# FPGA_JTAG.net
KiCad netlist of a schematic drawn in Altium Designer
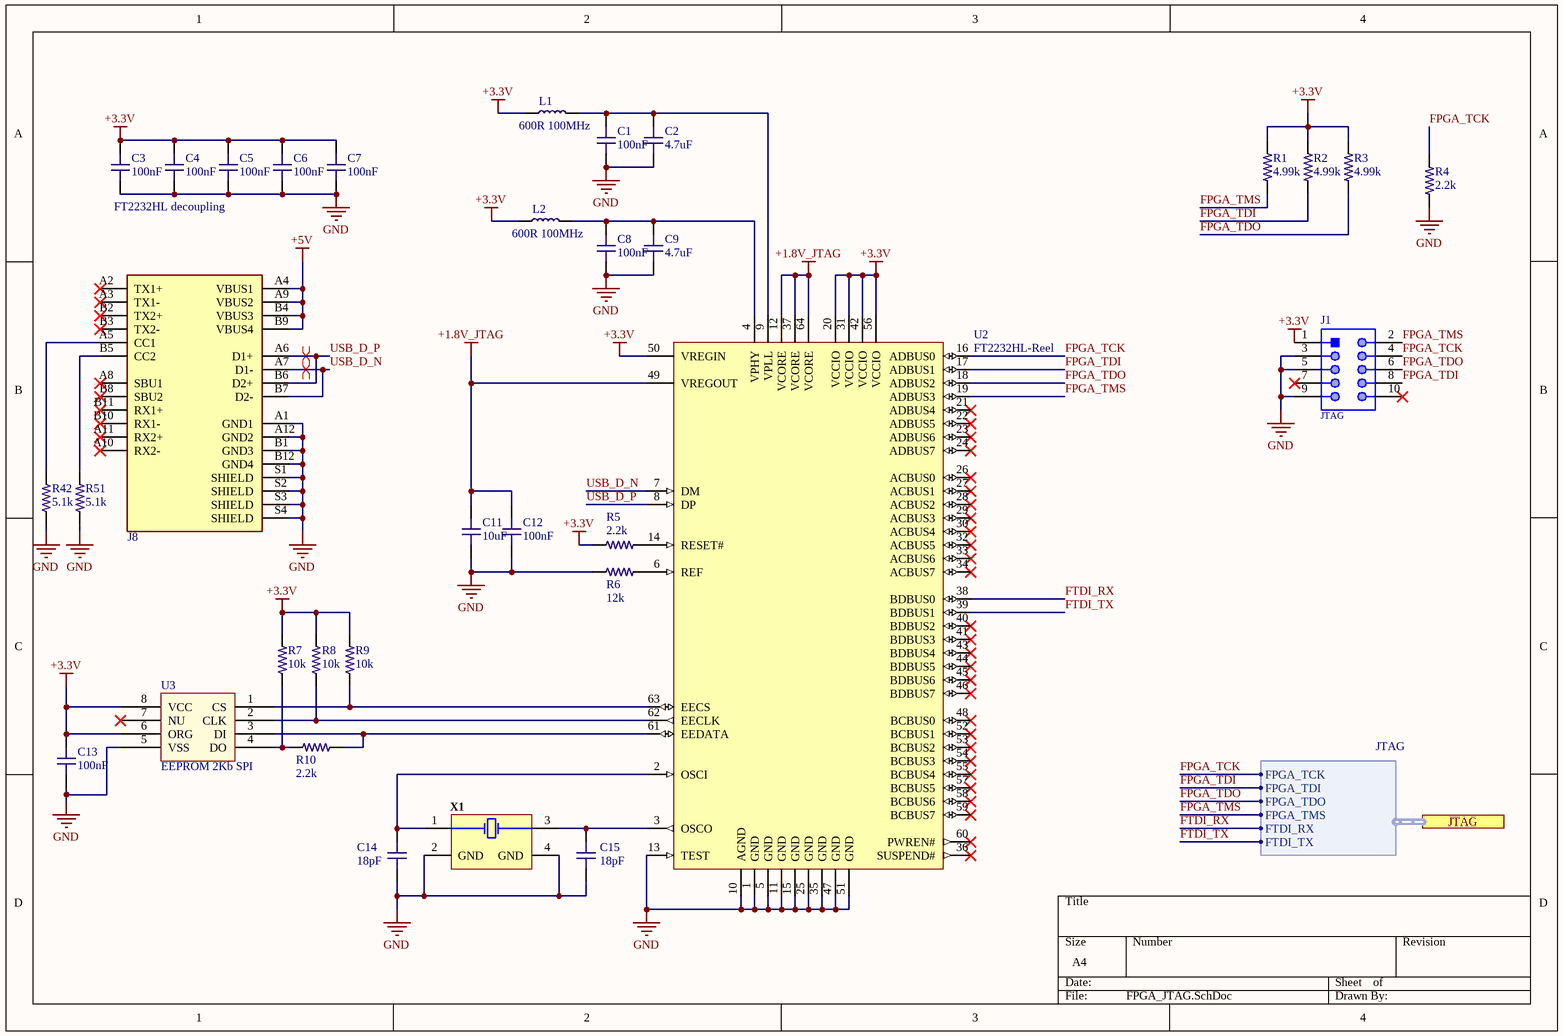
[diagram p0: FPGA_JTAG.SchDoc]

(export (version "E")
  (design (tool "Eeschema 10.0.6"))
  (components
    (comp (ref "C1")
      (value "100nF")
      (footprint "C0603-HIGH-DENSITY")
      (description "Chip Capacitor, 0603, 100nF, 25V, X7R")
      (fields (field (name "Comment") "C0603 100nF 25V X7R"))
      (libsource (lib "Capacitors") (part "C0603 100nF 25V X7R"))
    )
    (comp (ref "C2")
      (value "4.7uF")
      (footprint "C0603-HIGH-DENSITY")
      (description "Chip Capacitor, 0603, 4.7uF, 10V, X5R")
      (fields (field (name "Comment") "C0603 4.7uF 6.3V X5R"))
      (libsource (lib "Capacitors") (part "C0402 4.7uF 6.3V X5R"))
    )
    (comp (ref "C3")
      (value "100nF")
      (footprint "C0603-HIGH-DENSITY")
      (description "Chip Capacitor, 0603, 100nF, 25V, X7R")
      (fields (field (name "Comment") "C0603 100nF 25V X7R"))
      (libsource (lib "Capacitors") (part "C0603 100nF 25V X7R"))
    )
    (comp (ref "C4")
      (value "100nF")
      (footprint "C0603-HIGH-DENSITY")
      (description "Chip Capacitor, 0603, 100nF, 25V, X7R")
      (fields (field (name "Comment") "C0603 100nF 25V X7R"))
      (libsource (lib "Capacitors") (part "C0603 100nF 25V X7R"))
    )
    (comp (ref "C5")
      (value "100nF")
      (footprint "C0603-HIGH-DENSITY")
      (description "Chip Capacitor, 0603, 100nF, 25V, X7R")
      (fields (field (name "Comment") "C0603 100nF 25V X7R"))
      (libsource (lib "Capacitors") (part "C0603 100nF 25V X7R"))
    )
    (comp (ref "C6")
      (value "100nF")
      (footprint "C0603-HIGH-DENSITY")
      (description "Chip Capacitor, 0603, 100nF, 25V, X7R")
      (fields (field (name "Comment") "C0603 100nF 25V X7R"))
      (libsource (lib "Capacitors") (part "C0603 100nF 25V X7R"))
    )
    (comp (ref "C7")
      (value "100nF")
      (footprint "C0603-HIGH-DENSITY")
      (description "Chip Capacitor, 0603, 100nF, 25V, X7R")
      (fields (field (name "Comment") "C0603 100nF 25V X7R"))
      (libsource (lib "Capacitors") (part "C0603 100nF 25V X7R"))
    )
    (comp (ref "C8")
      (value "100nF")
      (footprint "C0603-HIGH-DENSITY")
      (description "Chip Capacitor, 0603, 100nF, 25V, X7R")
      (fields (field (name "Comment") "C0603 100nF 25V X7R"))
      (libsource (lib "Capacitors") (part "C0603 100nF 25V X7R"))
    )
    (comp (ref "C9")
      (value "4.7uF")
      (footprint "C0603-HIGH-DENSITY")
      (description "Chip Capacitor, 0603, 4.7uF, 10V, X5R")
      (fields (field (name "Comment") "C0603 4.7uF 6.3V X5R"))
      (libsource (lib "Capacitors") (part "C0402 4.7uF 6.3V X5R"))
    )
    (comp (ref "C11")
      (value "10uF")
      (footprint "C0603-HIGH-DENSITY")
      (description "Chip Capacitor, 0603, 10uF, 10V, X5R")
      (fields (field (name "Comment") "C0603 10uF 10V X5R"))
      (libsource (lib "Capacitors") (part "C0603 10uF 10V X5R"))
    )
    (comp (ref "C12")
      (value "100nF")
      (footprint "C0603-HIGH-DENSITY")
      (description "Chip Capacitor, 0603, 100nF, 25V, X7R")
      (fields (field (name "Comment") "C0603 100nF 25V X7R"))
      (libsource (lib "Capacitors") (part "C0603 100nF 25V X7R"))
    )
    (comp (ref "C13")
      (value "100nF")
      (footprint "C0603-HIGH-DENSITY")
      (description "Chip Capacitor, 0603, 100nF, 25V, X7R")
      (fields (field (name "Comment") "C0603 100nF 25V X7R"))
      (libsource (lib "Capacitors") (part "C0603 100nF 25V X7R"))
    )
    (comp (ref "C14")
      (value "18pF")
      (footprint "C0603-HIGH-DENSITY")
      (description "Chip Capacitor, 0603, 18pF, 25V, C0G")
      (fields (field (name "Comment") "C0603 18pF 50V C0G_1"))
      (libsource (lib "Capacitors") (part "C0402 18pF 50V C0G_1"))
    )
    (comp (ref "C15")
      (value "18pF")
      (footprint "C0603-HIGH-DENSITY")
      (description "Chip Capacitor, 0603, 18pF, 25V, C0G")
      (fields (field (name "Comment") "C0603 18pF 50V C0G_1"))
      (libsource (lib "Capacitors") (part "C0402 18pF 50V C0G_1"))
    )
    (comp (ref "J1")
      (value "JTAG")
      (footprint "61201021621")
      (description "Male Box Header WR-BHD, THT, Vertical, pitch 2.54 mm, 10 pins")
      (fields
        (field (name "PART NUMBER") "61201021621")
        (field (name "MANUFACTURER") "Wurth Elektronik")
        (field (name "PUBLISHER") "WurthElektronik")
      )
      (libsource (lib "Altium Content Vault") (part "WE-CN-2P-M-R10"))
    )
    (comp (ref "J8")
      (value "USB C")
      (footprint "Molex USB-C")
      (fields
        (field (name "MF") "Molex")
        (field (name "DIGI-KEY_PART_NUMBER") "WM12856CT-ND")
        (field (name "MP") "1054500101")
      )
      (libsource (lib "Connectors") (part "USB C"))
    )
    (comp (ref "L1")
      (value "600R 100MHz")
      (footprint "L0603")
      (description "600 Ohms @ 100MHz 1 Ferrite Bead 0603 (1608 Metric) 500mA 380mOhm")
      (fields (field (name "Comment") "Ferrite Bead"))
      (libsource (lib "Inductors") (part "FB 0603 600R @ 100MHz"))
    )
    (comp (ref "L2")
      (value "600R 100MHz")
      (footprint "L0603")
      (description "600 Ohms @ 100MHz 1 Ferrite Bead 0603 (1608 Metric) 500mA 380mOhm")
      (fields (field (name "Comment") "Ferrite Bead"))
      (libsource (lib "Inductors") (part "FB 0603 600R @ 100MHz"))
    )
    (comp (ref "R1")
      (value "4.99k")
      (footprint "R0603-HIGH-DENSITY")
      (description "RES SMD 4.99KOHM 0.1% 1/10W 0603")
      (fields (field (name "TOLERANCE") "±0.1%") (field (name "Comment") "R0603 4.99K 0.1%"))
      (libsource (lib "Resistors") (part "R0603 4.99K 0.1%"))
    )
    (comp (ref "R2")
      (value "4.99k")
      (footprint "R0603-HIGH-DENSITY")
      (description "RES SMD 4.99KOHM 0.1% 1/10W 0603")
      (fields (field (name "TOLERANCE") "±0.1%") (field (name "Comment") "R0603 4.99K 0.1%"))
      (libsource (lib "Resistors") (part "R0603 4.99K 0.1%"))
    )
    (comp (ref "R3")
      (value "4.99k")
      (footprint "R0603-HIGH-DENSITY")
      (description "RES SMD 4.99KOHM 0.1% 1/10W 0603")
      (fields (field (name "TOLERANCE") "±0.1%") (field (name "Comment") "R0603 4.99K 0.1%"))
      (libsource (lib "Resistors") (part "R0603 4.99K 0.1%"))
    )
    (comp (ref "R4")
      (value "2.2k")
      (footprint "R0603-HIGH-DENSITY")
      (description "RES SMD 2.2K OHM 1% 1/10W 0603")
      (fields (field (name "Comment") "R0603 2.2K 1%"))
      (libsource (lib "Resistors") (part "R0603 2.2K 1%"))
    )
    (comp (ref "R5")
      (value "2.2k")
      (footprint "R0603-HIGH-DENSITY")
      (description "RES SMD 2.2K OHM 1% 1/10W 0603")
      (fields (field (name "Comment") "R0603 2.2K 1%"))
      (libsource (lib "Resistors") (part "R0603 2.2K 1%"))
    )
    (comp (ref "R6")
      (value "12k")
      (footprint "R0603-HIGH-DENSITY")
      (description "RES 12K OHM 1% 1/10W 0603")
      (fields (field (name "Comment") "R0603 12k 1%"))
      (libsource (lib "Resistors") (part "R0603 12k 1%"))
    )
    (comp (ref "R7")
      (value "10k")
      (footprint "R0603-IPC")
      (description "RES SMD 10K OHM 1% 1/10W 0603")
      (fields (field (name "Comment") "R0603 10K 1%"))
      (libsource (lib "Resistors") (part "R0603 10K 1%"))
    )
    (comp (ref "R8")
      (value "10k")
      (footprint "R0603-IPC")
      (description "RES SMD 10K OHM 1% 1/10W 0603")
      (fields (field (name "Comment") "R0603 10K 1%"))
      (libsource (lib "Resistors") (part "R0603 10K 1%"))
    )
    (comp (ref "R9")
      (value "10k")
      (footprint "R0603-IPC")
      (description "RES SMD 10K OHM 1% 1/10W 0603")
      (fields (field (name "Comment") "R0603 10K 1%"))
      (libsource (lib "Resistors") (part "R0603 10K 1%"))
    )
    (comp (ref "R10")
      (value "2.2k")
      (footprint "R0603-IPC")
      (description "RES SMD 2.2K OHM 1% 1/10W 0603")
      (fields (field (name "Comment") "R0603 2.2K 1%"))
      (libsource (lib "Resistors") (part "R0603 2.2K 1%"))
    )
    (comp (ref "R42")
      (value "5.1k")
      (footprint "R0603-IPC-5.1K")
      (description "RES SMD 5.1K OHM 1% 1/10W 0603")
      (fields (field (name "Comment") "R0603 5.1K 1%"))
      (libsource (lib "Resistors") (part "R0603 5.1K 1%"))
    )
    (comp (ref "R51")
      (value "5.1k")
      (footprint "R0603-IPC-5.1K")
      (description "RES SMD 5.1K OHM 1% 1/10W 0603")
      (fields (field (name "Comment") "R0603 5.1K 1%"))
      (libsource (lib "Resistors") (part "R0603 5.1K 1%"))
    )
    (comp (ref "U2")
      (value "FT2232HL-Reel")
      (footprint "LQFP-64_M")
      (description "Dual High Speed USB To Multipurpose UART/FIFO IC, 64-pin LQFP, Tape and Reel")
      (fields (field (name "MANUFACTURER") "FTDI"))
      (libsource (lib "Altium Content Vault") (part "COM-UART-FT2232H-LQFP64"))
    )
    (comp (ref "U3")
      (value "EEPROM 2Kb SPI")
      (footprint "SOIC127P600X175-8N")
      (description "EEPROM Memory IC 2Kb (256 x 8, 128 x 16) SPI 3MHz 8-SOIC")
      (libsource (lib "Integrated Circuits") (part "93LC56C-I/SN"))
    )
    (comp (ref "X1")
      (value "ABM8G-12.000MHZ-18-D2Y-T")
      (footprint "ABRACON_ABM8G_V")
      (fields (field (name "TOLERANCE") "20PPM") (field (name "MANUFACTURER") "ABRACON"))
      (libsource (lib "Altium Content Vault") (part "XTAL-1-3-4"))
    )
  )
  (nets
    (net (code "2") (name "+1.8V_JTAG") (class "Default")
      (node (ref "C11") (pin "2") (pintype "passive"))
      (node (ref "C12") (pin "2") (pintype "passive"))
      (node (ref "U2") (pin "12") (pinfunction "VCORE_12") (pintype "power_in"))
      (node (ref "U2") (pin "37") (pinfunction "VCORE_37") (pintype "power_in"))
      (node (ref "U2") (pin "49") (pinfunction "VREGOUT_49") (pintype "power_in"))
      (node (ref "U2") (pin "64") (pinfunction "VCORE_64") (pintype "power_in"))
    )
    (net (code "3") (name "+3.3V") (class "Default")
      (node (ref "C13") (pin "2") (pintype "passive"))
      (node (ref "C3") (pin "2") (pintype "passive"))
      (node (ref "C4") (pin "2") (pintype "passive"))
      (node (ref "C5") (pin "2") (pintype "passive"))
      (node (ref "C6") (pin "2") (pintype "passive"))
      (node (ref "C7") (pin "2") (pintype "passive"))
      (node (ref "J1") (pin "1") (pinfunction "1_1") (pintype "passive"))
      (node (ref "L1") (pin "1") (pintype "passive"))
      (node (ref "L2") (pin "1") (pintype "passive"))
      (node (ref "R1") (pin "2") (pintype "passive"))
      (node (ref "R2") (pin "2") (pintype "passive"))
      (node (ref "R3") (pin "2") (pintype "passive"))
      (node (ref "R5") (pin "2") (pintype "passive"))
      (node (ref "R7") (pin "2") (pintype "passive"))
      (node (ref "R8") (pin "2") (pintype "passive"))
      (node (ref "R9") (pin "2") (pintype "passive"))
      (node (ref "U2") (pin "20") (pinfunction "VCCIO_20") (pintype "power_in"))
      (node (ref "U2") (pin "31") (pinfunction "VCCIO_31") (pintype "power_in"))
      (node (ref "U2") (pin "42") (pinfunction "VCCIO_42") (pintype "power_in"))
      (node (ref "U2") (pin "50") (pinfunction "VREGIN_50") (pintype "power_in"))
      (node (ref "U2") (pin "56") (pinfunction "VCCIO_56") (pintype "power_in"))
      (node (ref "U3") (pin "6") (pinfunction "ORG_6") (pintype "passive"))
      (node (ref "U3") (pin "8") (pinfunction "VCC_8") (pintype "passive"))
    )
    (net (code "4") (name "+5V") (class "Default")
      (node (ref "J8") (pin "A4") (pinfunction "VBUS1_A4") (pintype "passive"))
      (node (ref "J8") (pin "A9") (pinfunction "VBUS2_A9") (pintype "passive"))
      (node (ref "J8") (pin "B4") (pinfunction "VBUS3_B4") (pintype "passive"))
      (node (ref "J8") (pin "B9") (pinfunction "VBUS4_B9") (pintype "passive"))
    )
    (net (code "5") (name "/FPGA_TCK") (class "Default")
      (node (ref "J1") (pin "4") (pinfunction "4_4") (pintype "passive"))
      (node (ref "R4") (pin "2") (pintype "passive"))
      (node (ref "U2") (pin "16") (pinfunction "ADBUS0_16") (pintype "bidirectional"))
    )
    (net (code "6") (name "/FPGA_TDI") (class "Default")
      (node (ref "J1") (pin "8") (pinfunction "8_8") (pintype "passive"))
      (node (ref "R2") (pin "1") (pintype "passive"))
      (node (ref "U2") (pin "17") (pinfunction "ADBUS1_17") (pintype "bidirectional"))
    )
    (net (code "7") (name "/FPGA_TDO") (class "Default")
      (node (ref "J1") (pin "6") (pinfunction "6_6") (pintype "passive"))
      (node (ref "R3") (pin "1") (pintype "passive"))
      (node (ref "U2") (pin "18") (pinfunction "ADBUS2_18") (pintype "bidirectional"))
    )
    (net (code "8") (name "/FPGA_TMS") (class "Default")
      (node (ref "J1") (pin "2") (pinfunction "2_2") (pintype "passive"))
      (node (ref "R1") (pin "1") (pintype "passive"))
      (node (ref "U2") (pin "19") (pinfunction "ADBUS3_19") (pintype "bidirectional"))
    )
    (net (code "9") (name "/FTDI_RX") (class "Default")
      (node (ref "U2") (pin "38") (pinfunction "BDBUS0_38") (pintype "bidirectional"))
    )
    (net (code "10") (name "/FTDI_TX") (class "Default")
      (node (ref "U2") (pin "39") (pinfunction "BDBUS1_39") (pintype "bidirectional"))
    )
    (net (code "11") (name "/USB_D_N") (class "Default")
      (node (ref "J8") (pin "A7") (pinfunction "D1-_A7") (pintype "passive"))
      (node (ref "J8") (pin "B7") (pinfunction "D2-_B7") (pintype "passive"))
      (node (ref "U2") (pin "7") (pinfunction "DM_7") (pintype "input"))
    )
    (net (code "12") (name "/USB_D_P") (class "Default")
      (node (ref "J8") (pin "A6") (pinfunction "D1+_A6") (pintype "passive"))
      (node (ref "J8") (pin "B6") (pinfunction "D2+_B6") (pintype "passive"))
      (node (ref "U2") (pin "8") (pinfunction "DP_8") (pintype "input"))
    )
    (net (code "14") (name "GND") (class "Default")
      (node (ref "C1") (pin "1") (pintype "passive"))
      (node (ref "C11") (pin "1") (pintype "passive"))
      (node (ref "C12") (pin "1") (pintype "passive"))
      (node (ref "C13") (pin "1") (pintype "passive"))
      (node (ref "C14") (pin "1") (pintype "passive"))
      (node (ref "C15") (pin "1") (pintype "passive"))
      (node (ref "C2") (pin "1") (pintype "passive"))
      (node (ref "C3") (pin "1") (pintype "passive"))
      (node (ref "C4") (pin "1") (pintype "passive"))
      (node (ref "C5") (pin "1") (pintype "passive"))
      (node (ref "C6") (pin "1") (pintype "passive"))
      (node (ref "C7") (pin "1") (pintype "passive"))
      (node (ref "C8") (pin "1") (pintype "passive"))
      (node (ref "C9") (pin "1") (pintype "passive"))
      (node (ref "J1") (pin "3") (pinfunction "3_3") (pintype "passive"))
      (node (ref "J1") (pin "5") (pinfunction "5_5") (pintype "passive"))
      (node (ref "J1") (pin "9") (pinfunction "9_9") (pintype "passive"))
      (node (ref "J8") (pin "A1") (pinfunction "GND1_A1") (pintype "passive"))
      (node (ref "J8") (pin "A12") (pinfunction "GND2_A12") (pintype "passive"))
      (node (ref "J8") (pin "B1") (pinfunction "GND3_B1") (pintype "passive"))
      (node (ref "J8") (pin "B12") (pinfunction "GND4_B12") (pintype "passive"))
      (node (ref "J8") (pin "S1") (pinfunction "SHIELD_S1") (pintype "passive"))
      (node (ref "J8") (pin "S2") (pinfunction "SHIELD_S2") (pintype "passive"))
      (node (ref "J8") (pin "S3") (pinfunction "SHIELD_S3") (pintype "passive"))
      (node (ref "J8") (pin "S4") (pinfunction "SHIELD_S4") (pintype "passive"))
      (node (ref "R4") (pin "1") (pintype "passive"))
      (node (ref "R42") (pin "1") (pintype "passive"))
      (node (ref "R51") (pin "1") (pintype "passive"))
      (node (ref "R6") (pin "1") (pintype "passive"))
      (node (ref "U2") (pin "1") (pinfunction "GND_1") (pintype "power_in"))
      (node (ref "U2") (pin "10") (pinfunction "AGND_10") (pintype "power_in"))
      (node (ref "U2") (pin "11") (pinfunction "GND_11") (pintype "power_in"))
      (node (ref "U2") (pin "13") (pinfunction "TEST_13") (pintype "input"))
      (node (ref "U2") (pin "15") (pinfunction "GND_15") (pintype "power_in"))
      (node (ref "U2") (pin "25") (pinfunction "GND_25") (pintype "power_in"))
      (node (ref "U2") (pin "35") (pinfunction "GND_35") (pintype "power_in"))
      (node (ref "U2") (pin "47") (pinfunction "GND_47") (pintype "power_in"))
      (node (ref "U2") (pin "5") (pinfunction "GND_5") (pintype "power_in"))
      (node (ref "U2") (pin "51") (pinfunction "GND_51") (pintype "power_in"))
      (node (ref "U3") (pin "5") (pinfunction "VSS_5") (pintype "passive"))
      (node (ref "X1") (pin "2") (pinfunction "GND_2") (pintype "power_in"))
      (node (ref "X1") (pin "4") (pinfunction "GND_4") (pintype "power_in"))
    )
    (net (code "15") (name "Net-(J8-CC1)") (class "Default")
      (node (ref "J8") (pin "A5") (pinfunction "CC1_A5") (pintype "passive"))
      (node (ref "R42") (pin "2") (pintype "passive"))
    )
    (net (code "16") (name "Net-(J8-CC2)") (class "Default")
      (node (ref "J8") (pin "B5") (pinfunction "CC2_B5") (pintype "passive"))
      (node (ref "R51") (pin "2") (pintype "passive"))
    )
    (net (code "17") (name "Net-(U2-EECLK)") (class "Default")
      (node (ref "R8") (pin "1") (pintype "passive"))
      (node (ref "U2") (pin "62") (pinfunction "EECLK_62") (pintype "output"))
      (node (ref "U3") (pin "2") (pinfunction "CLK_2") (pintype "passive"))
    )
    (net (code "18") (name "Net-(U2-EECS)") (class "Default")
      (node (ref "R9") (pin "1") (pintype "passive"))
      (node (ref "U2") (pin "63") (pinfunction "EECS_63") (pintype "bidirectional"))
      (node (ref "U3") (pin "1") (pinfunction "CS_1") (pintype "passive"))
    )
    (net (code "19") (name "Net-(U2-EEDATA)") (class "Default")
      (node (ref "R10") (pin "1") (pintype "passive"))
      (node (ref "U2") (pin "61") (pinfunction "EEDATA_61") (pintype "bidirectional"))
      (node (ref "U3") (pin "3") (pinfunction "DI_3") (pintype "passive"))
    )
    (net (code "20") (name "Net-(U2-OSCI)") (class "Default")
      (node (ref "C14") (pin "2") (pintype "passive"))
      (node (ref "U2") (pin "2") (pinfunction "OSCI_2") (pintype "input"))
      (node (ref "X1") (pin "1") (pinfunction "X1_1") (pintype "passive"))
    )
    (net (code "21") (name "Net-(U2-OSCO)") (class "Default")
      (node (ref "C15") (pin "2") (pintype "passive"))
      (node (ref "U2") (pin "3") (pinfunction "OSCO_3") (pintype "output"))
      (node (ref "X1") (pin "3") (pinfunction "X2_3") (pintype "passive"))
    )
    (net (code "22") (name "Net-(U2-REF)") (class "Default")
      (node (ref "R6") (pin "2") (pintype "passive"))
      (node (ref "U2") (pin "6") (pinfunction "REF_6") (pintype "input"))
    )
    (net (code "23") (name "Net-(U2-RESET#)") (class "Default")
      (node (ref "R5") (pin "1") (pintype "passive"))
      (node (ref "U2") (pin "14") (pinfunction "RESET#_14") (pintype "input"))
    )
    (net (code "24") (name "Net-(U2-VPHY)") (class "Default")
      (node (ref "C8") (pin "2") (pintype "passive"))
      (node (ref "C9") (pin "2") (pintype "passive"))
      (node (ref "L2") (pin "2") (pintype "passive"))
      (node (ref "U2") (pin "4") (pinfunction "VPHY_4") (pintype "power_in"))
    )
    (net (code "25") (name "Net-(U2-VPLL)") (class "Default")
      (node (ref "C1") (pin "2") (pintype "passive"))
      (node (ref "C2") (pin "2") (pintype "passive"))
      (node (ref "L1") (pin "2") (pintype "passive"))
      (node (ref "U2") (pin "9") (pinfunction "VPLL_9") (pintype "power_in"))
    )
    (net (code "26") (name "Net-(U3-DO)") (class "Default")
      (node (ref "R10") (pin "2") (pintype "passive"))
      (node (ref "R7") (pin "1") (pintype "passive"))
      (node (ref "U3") (pin "4") (pinfunction "DO_4") (pintype "passive"))
    )
    (net (code "27") (name "unconnected-(J1-Pad7)") (class "Default")
      (node (ref "J1") (pin "7") (pinfunction "7_7") (pintype "passive+no_connect"))
    )
    (net (code "28") (name "unconnected-(J1-Pad10)") (class "Default")
      (node (ref "J1") (pin "10") (pinfunction "10_10") (pintype "passive+no_connect"))
    )
    (net (code "29") (name "unconnected-(J8-RX1+-PadB11)") (class "Default")
      (node (ref "J8") (pin "B11") (pinfunction "RX1+_B11") (pintype "passive+no_connect"))
    )
    (net (code "30") (name "unconnected-(J8-RX1--PadB10)") (class "Default")
      (node (ref "J8") (pin "B10") (pinfunction "RX1-_B10") (pintype "passive+no_connect"))
    )
    (net (code "31") (name "unconnected-(J8-RX2+-PadA11)") (class "Default")
      (node (ref "J8") (pin "A11") (pinfunction "RX2+_A11") (pintype "passive+no_connect"))
    )
    (net (code "32") (name "unconnected-(J8-RX2--PadA10)") (class "Default")
      (node (ref "J8") (pin "A10") (pinfunction "RX2-_A10") (pintype "passive+no_connect"))
    )
    (net (code "33") (name "unconnected-(J8-SBU1-PadA8)") (class "Default")
      (node (ref "J8") (pin "A8") (pinfunction "SBU1_A8") (pintype "passive+no_connect"))
    )
    (net (code "34") (name "unconnected-(J8-SBU2-PadB8)") (class "Default")
      (node (ref "J8") (pin "B8") (pinfunction "SBU2_B8") (pintype "passive+no_connect"))
    )
    (net (code "35") (name "unconnected-(J8-TX1+-PadA2)") (class "Default")
      (node (ref "J8") (pin "A2") (pinfunction "TX1+_A2") (pintype "passive+no_connect"))
    )
    (net (code "36") (name "unconnected-(J8-TX1--PadA3)") (class "Default")
      (node (ref "J8") (pin "A3") (pinfunction "TX1-_A3") (pintype "passive+no_connect"))
    )
    (net (code "37") (name "unconnected-(J8-TX2+-PadB2)") (class "Default")
      (node (ref "J8") (pin "B2") (pinfunction "TX2+_B2") (pintype "passive+no_connect"))
    )
    (net (code "38") (name "unconnected-(J8-TX2--PadB3)") (class "Default")
      (node (ref "J8") (pin "B3") (pinfunction "TX2-_B3") (pintype "passive+no_connect"))
    )
    (net (code "39") (name "unconnected-(U2-ACBUS0-Pad26)") (class "Default")
      (node (ref "U2") (pin "26") (pinfunction "ACBUS0_26") (pintype "bidirectional+no_connect"))
    )
    (net (code "40") (name "unconnected-(U2-ACBUS1-Pad27)") (class "Default")
      (node (ref "U2") (pin "27") (pinfunction "ACBUS1_27") (pintype "bidirectional+no_connect"))
    )
    (net (code "41") (name "unconnected-(U2-ACBUS2-Pad28)") (class "Default")
      (node (ref "U2") (pin "28") (pinfunction "ACBUS2_28") (pintype "bidirectional+no_connect"))
    )
    (net (code "42") (name "unconnected-(U2-ACBUS3-Pad29)") (class "Default")
      (node (ref "U2") (pin "29") (pinfunction "ACBUS3_29") (pintype "bidirectional+no_connect"))
    )
    (net (code "43") (name "unconnected-(U2-ACBUS4-Pad30)") (class "Default")
      (node (ref "U2") (pin "30") (pinfunction "ACBUS4_30") (pintype "bidirectional+no_connect"))
    )
    (net (code "44") (name "unconnected-(U2-ACBUS5-Pad32)") (class "Default")
      (node (ref "U2") (pin "32") (pinfunction "ACBUS5_32") (pintype "bidirectional+no_connect"))
    )
    (net (code "45") (name "unconnected-(U2-ACBUS6-Pad33)") (class "Default")
      (node (ref "U2") (pin "33") (pinfunction "ACBUS6_33") (pintype "bidirectional+no_connect"))
    )
    (net (code "46") (name "unconnected-(U2-ACBUS7-Pad34)") (class "Default")
      (node (ref "U2") (pin "34") (pinfunction "ACBUS7_34") (pintype "bidirectional+no_connect"))
    )
    (net (code "47") (name "unconnected-(U2-ADBUS4-Pad21)") (class "Default")
      (node (ref "U2") (pin "21") (pinfunction "ADBUS4_21") (pintype "bidirectional+no_connect"))
    )
    (net (code "48") (name "unconnected-(U2-ADBUS5-Pad22)") (class "Default")
      (node (ref "U2") (pin "22") (pinfunction "ADBUS5_22") (pintype "bidirectional+no_connect"))
    )
    (net (code "49") (name "unconnected-(U2-ADBUS6-Pad23)") (class "Default")
      (node (ref "U2") (pin "23") (pinfunction "ADBUS6_23") (pintype "bidirectional+no_connect"))
    )
    (net (code "50") (name "unconnected-(U2-ADBUS7-Pad24)") (class "Default")
      (node (ref "U2") (pin "24") (pinfunction "ADBUS7_24") (pintype "bidirectional+no_connect"))
    )
    (net (code "51") (name "unconnected-(U2-BCBUS0-Pad48)") (class "Default")
      (node (ref "U2") (pin "48") (pinfunction "BCBUS0_48") (pintype "bidirectional+no_connect"))
    )
    (net (code "52") (name "unconnected-(U2-BCBUS1-Pad52)") (class "Default")
      (node (ref "U2") (pin "52") (pinfunction "BCBUS1_52") (pintype "bidirectional+no_connect"))
    )
    (net (code "53") (name "unconnected-(U2-BCBUS2-Pad53)") (class "Default")
      (node (ref "U2") (pin "53") (pinfunction "BCBUS2_53") (pintype "bidirectional+no_connect"))
    )
    (net (code "54") (name "unconnected-(U2-BCBUS3-Pad54)") (class "Default")
      (node (ref "U2") (pin "54") (pinfunction "BCBUS3_54") (pintype "bidirectional+no_connect"))
    )
    (net (code "55") (name "unconnected-(U2-BCBUS4-Pad55)") (class "Default")
      (node (ref "U2") (pin "55") (pinfunction "BCBUS4_55") (pintype "bidirectional+no_connect"))
    )
    (net (code "56") (name "unconnected-(U2-BCBUS5-Pad57)") (class "Default")
      (node (ref "U2") (pin "57") (pinfunction "BCBUS5_57") (pintype "bidirectional+no_connect"))
    )
    (net (code "57") (name "unconnected-(U2-BCBUS6-Pad58)") (class "Default")
      (node (ref "U2") (pin "58") (pinfunction "BCBUS6_58") (pintype "bidirectional+no_connect"))
    )
    (net (code "58") (name "unconnected-(U2-BCBUS7-Pad59)") (class "Default")
      (node (ref "U2") (pin "59") (pinfunction "BCBUS7_59") (pintype "bidirectional+no_connect"))
    )
    (net (code "59") (name "unconnected-(U2-BDBUS2-Pad40)") (class "Default")
      (node (ref "U2") (pin "40") (pinfunction "BDBUS2_40") (pintype "bidirectional+no_connect"))
    )
    (net (code "60") (name "unconnected-(U2-BDBUS3-Pad41)") (class "Default")
      (node (ref "U2") (pin "41") (pinfunction "BDBUS3_41") (pintype "bidirectional+no_connect"))
    )
    (net (code "61") (name "unconnected-(U2-BDBUS4-Pad43)") (class "Default")
      (node (ref "U2") (pin "43") (pinfunction "BDBUS4_43") (pintype "bidirectional+no_connect"))
    )
    (net (code "62") (name "unconnected-(U2-BDBUS5-Pad44)") (class "Default")
      (node (ref "U2") (pin "44") (pinfunction "BDBUS5_44") (pintype "bidirectional+no_connect"))
    )
    (net (code "63") (name "unconnected-(U2-BDBUS6-Pad45)") (class "Default")
      (node (ref "U2") (pin "45") (pinfunction "BDBUS6_45") (pintype "bidirectional+no_connect"))
    )
    (net (code "64") (name "unconnected-(U2-BDBUS7-Pad46)") (class "Default")
      (node (ref "U2") (pin "46") (pinfunction "BDBUS7_46") (pintype "bidirectional+no_connect"))
    )
    (net (code "65") (name "unconnected-(U2-PWREN#-Pad60)") (class "Default")
      (node (ref "U2") (pin "60") (pinfunction "PWREN#_60") (pintype "output+no_connect"))
    )
    (net (code "66") (name "unconnected-(U2-SUSPEND#-Pad36)") (class "Default")
      (node (ref "U2") (pin "36") (pinfunction "SUSPEND#_36") (pintype "output+no_connect"))
    )
    (net (code "67") (name "unconnected-(U3-NU-Pad7)") (class "Default")
      (node (ref "U3") (pin "7") (pinfunction "NU_7") (pintype "passive+no_connect"))
    )
  )
)
